# -STM32F1-3_0.net
KiCad netlist of a schematic drawn in EasyEDA Pro
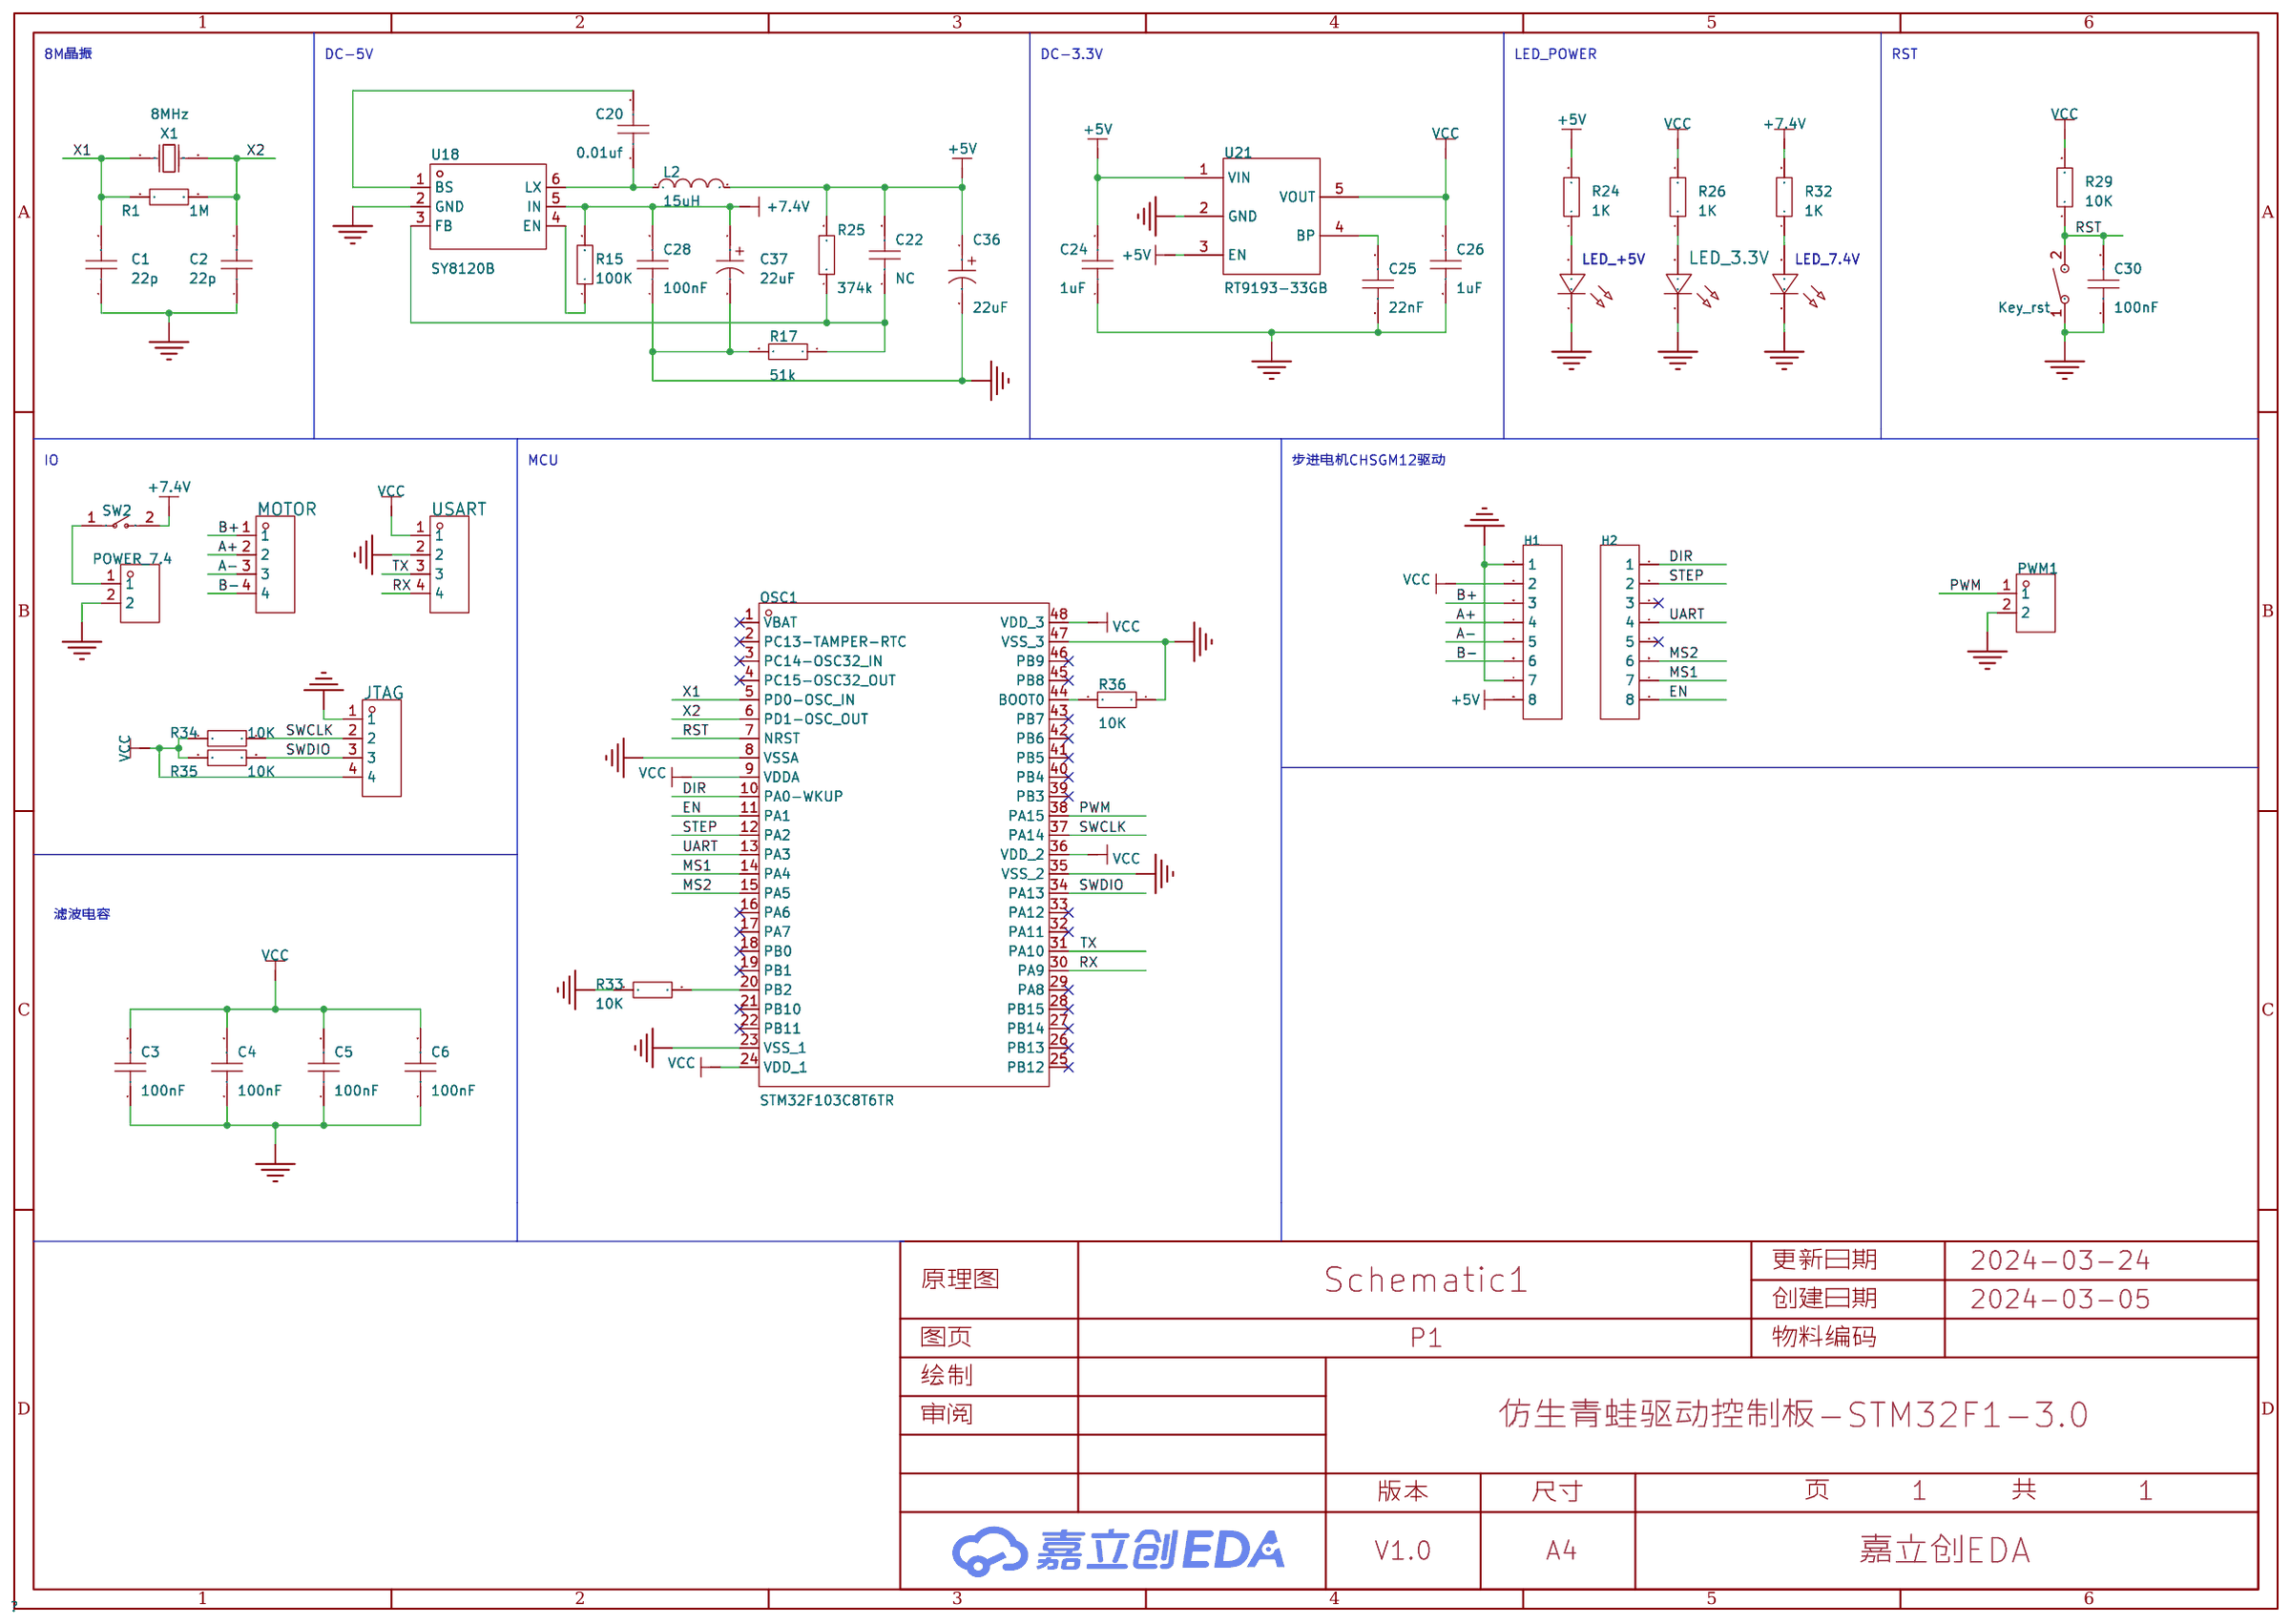
[diagram p0: schematic sheet]

(export (version "E")
  (design (tool "Eeschema 10.0.6"))
  (components
    (comp (ref "C1")
      (value "22p")
      (footprint "easyedapro:c0603")
      (libsource (lib "easyedapro") (part "CapAcitance"))
    )
    (comp (ref "C2")
      (value "22p")
      (footprint "easyedapro:c0603")
      (libsource (lib "easyedapro") (part "CapAcitance"))
    )
    (comp (ref "C3")
      (value "100nF")
      (footprint "easyedapro:c0603")
      (libsource (lib "easyedapro") (part "CapAcitance"))
    )
    (comp (ref "C4")
      (value "100nF")
      (footprint "easyedapro:c0603")
      (libsource (lib "easyedapro") (part "CapAcitance"))
    )
    (comp (ref "C5")
      (value "100nF")
      (footprint "easyedapro:c0603")
      (libsource (lib "easyedapro") (part "CapAcitance"))
    )
    (comp (ref "C6")
      (value "100nF")
      (footprint "easyedapro:c0603")
      (libsource (lib "easyedapro") (part "CapAcitance"))
    )
    (comp (ref "C20")
      (value "0.01uf")
      (footprint "easyedapro:C0805")
      (libsource (lib "easyedapro") (part "CapAcitance"))
    )
    (comp (ref "C22")
      (value "NC")
      (footprint "easyedapro:C0805")
      (libsource (lib "easyedapro") (part "CapAcitance"))
    )
    (comp (ref "C24")
      (value "1uF")
      (footprint "easyedapro:c0603")
      (libsource (lib "easyedapro") (part "CapAcitance"))
    )
    (comp (ref "C25")
      (value "22nF")
      (footprint "easyedapro:c0603")
      (libsource (lib "easyedapro") (part "CapAcitance"))
    )
    (comp (ref "C26")
      (value "1uF")
      (footprint "easyedapro:c0603")
      (libsource (lib "easyedapro") (part "CapAcitance"))
    )
    (comp (ref "C28")
      (value "100nF")
      (footprint "easyedapro:c0603")
      (libsource (lib "easyedapro") (part "CapAcitance"))
    )
    (comp (ref "C30")
      (value "100nF")
      (footprint "easyedapro:c0603")
      (libsource (lib "easyedapro") (part "CapAcitance"))
    )
    (comp (ref "C36")
      (value "22uF")
      (footprint "easyedapro:CAP-SMD_BD5.0-L5.3-W5.3-LS6.0-FD")
      (description "容值:22uF;精度:±20%;额定电压:25V;纹波电流:26mA@120Hz;等效串联电阻:-;")
      (fields
        (field (name "Manufacturer Part") "RVT22UF25V67RV0047")
        (field (name "Manufacturer") "KNSCHA(科尼盛)")
      )
      (libsource (lib "easyedapro") (part "RVT22UF25V67RV0047"))
    )
    (comp (ref "C37")
      (value "22uF")
      (footprint "easyedapro:CAP-SMD_BD5.0-L5.3-W5.3-LS6.0-FD")
      (description "容值:22uF;精度:±20%;额定电压:25V;纹波电流:26mA@120Hz;等效串联电阻:-;")
      (fields
        (field (name "Manufacturer Part") "RVT22UF25V67RV0047")
        (field (name "Manufacturer") "KNSCHA(科尼盛)")
      )
      (libsource (lib "easyedapro") (part "RVT22UF25V67RV0047"))
    )
    (comp (ref "H1")
      (value "~")
      (footprint "easyedapro:HDR-TH_8P-P2.54-V-F-1")
      (libsource (lib "easyedapro") (part "Header-Female-2.54_1x8"))
    )
    (comp (ref "H2")
      (value "~")
      (footprint "easyedapro:HDR-TH_8P-P2.54-V-F-1")
      (libsource (lib "easyedapro") (part "Header-Female-2.54_1x8"))
    )
    (comp (ref "JTAG")
      (value "~")
      (footprint "easyedapro:HDR-TH_4P-P2.54-V-F")
      (libsource (lib "easyedapro") (part "2.54-1*4P母"))
    )
    (comp (ref "Key_rst")
      (value "TS-1092S-B3D2-G")
      (footprint "easyedapro:SW-SMD_L6.1-W3.6-LS7.9")
      (description "电路结构:单刀单掷;按钮形状:矩形按钮;作用力:250gf;安装方式:立贴;开关长度:6.1mm;开关宽度:3.6mm;开关高度:2.5mm;带支架:不带;机械寿命:-;")
      (fields (field (name "Manufacturer") "Yuandi(元迪)"))
      (libsource (lib "easyedapro") (part "TS-1092S-B3D2-G"))
    )
    (comp (ref "L2")
      (value "15uH")
      (footprint "easyedapro:IND-SMD_L7.0-W6.6_FXL0630")
      (description "电感值:15uH;精度:±20%;额定电流:3A;饱和电流(Isat):4.5A;类型:一体成型电感;")
      (fields (field (name "Manufacturer Part") "FXL0630-150-M") (field (name "Manufacturer") "cjiang(长江微电)"))
      (libsource (lib "easyedapro") (part "FXL0630-150-M"))
    )
    (comp (ref "LED_+5V")
      (value "~")
      (footprint "easyedapro:LED_0603")
      (libsource (lib "easyedapro") (part "LED_G"))
    )
    (comp (ref "LED_3.3V")
      (value "~")
      (footprint "easyedapro:LED_0402")
      (libsource (lib "easyedapro") (part "LED_R"))
    )
    (comp (ref "LED_7.4V")
      (value "~")
      (footprint "easyedapro:LED_0402")
      (libsource (lib "easyedapro") (part "LED_B"))
    )
    (comp (ref "MOTOR")
      (value "~")
      (footprint "easyedapro:HDR-TH_4P-P2.54-V-F")
      (libsource (lib "easyedapro") (part "2.54-1*4P母"))
    )
    (comp (ref "OSC1")
      (value "STM32F103C8T6TR")
      (footprint "easyedapro:LQFP-48_L7.0-W7.0-P0.50-LS9.0-BL")
      (description "CPU内核:CM3;程序存储容量:64KB;RAM总容量:20KB;GPIO端口数量:37;工作电压范围:2V~3.6V;CPU最大主频:72MHz;程序存储器类型:-;")
      (fields (field (name "Manufacturer") "ST(意法半导体)"))
      (libsource (lib "easyedapro") (part "STM32F103C8T6TR"))
    )
    (comp (ref "POWER_7.4")
      (value "ZX-XH2.54-2PZZ")
      (footprint "easyedapro:CONN-TH_2P-P2.50_HX25003-2A")
      (fields (field (name "Manufacturer") "Megastar(兆星)"))
      (libsource (lib "easyedapro") (part "ZX-XH2.54-2PZZ"))
    )
    (comp (ref "PWM1")
      (value "ZX-XH2.54-2PZZ")
      (footprint "easyedapro:CONN-TH_2P-P2.50_HX25003-2A")
      (fields (field (name "Manufacturer") "Megastar(兆星)"))
      (libsource (lib "easyedapro") (part "ZX-XH2.54-2PZZ"))
    )
    (comp (ref "R1") (value "1M") (footprint "easyedapro:r0603") (libsource (lib "easyedapro") (part "电阻")))
    (comp (ref "R15")
      (value "100K")
      (footprint "easyedapro:R0805")
      (libsource (lib "easyedapro") (part "电阻"))
    )
    (comp (ref "R17") (value "51k") (footprint "easyedapro:R0805") (libsource (lib "easyedapro") (part "电阻")))
    (comp (ref "R24") (value "1K") (footprint "easyedapro:R0805") (libsource (lib "easyedapro") (part "电阻")))
    (comp (ref "R25")
      (value "374k")
      (footprint "easyedapro:R0805")
      (libsource (lib "easyedapro") (part "电阻"))
    )
    (comp (ref "R26") (value "1K") (footprint "easyedapro:r0603") (libsource (lib "easyedapro") (part "电阻")))
    (comp (ref "R29") (value "10K") (footprint "easyedapro:r0603") (libsource (lib "easyedapro") (part "电阻")))
    (comp (ref "R32") (value "1K") (footprint "easyedapro:r0603") (libsource (lib "easyedapro") (part "电阻")))
    (comp (ref "R33") (value "10K") (footprint "easyedapro:r0603") (libsource (lib "easyedapro") (part "电阻")))
    (comp (ref "R34") (value "10K") (footprint "easyedapro:r0603") (libsource (lib "easyedapro") (part "电阻")))
    (comp (ref "R35") (value "10K") (footprint "easyedapro:r0603") (libsource (lib "easyedapro") (part "电阻")))
    (comp (ref "R36") (value "10K") (footprint "easyedapro:r0603") (libsource (lib "easyedapro") (part "电阻")))
    (comp (ref "SW2")
      (value "KCD11-2P-R")
      (footprint "easyedapro:SW-TH_2P-L15.0-W10.5-P5.00_KCD11-2P-R")
      (description "带灯:无;引脚样式:焊片;额定电流:3A;额定电压(AC):250V;额定电压(DC):-;电路结构:单刀单掷;机械寿命:1万次;")
      (fields (field (name "Manufacturer") "SHOU HAN(首韩)"))
      (libsource (lib "easyedapro") (part "KCD11-2P-R"))
    )
    (comp (ref "U18")
      (value "SY8120B")
      (footprint "easyedapro:SOT-23-6_L2.9-W1.6-P0.95-LS2.8-BL")
      (fields (field (name "Manufacturer") "Slkor(萨科微)"))
      (libsource (lib "easyedapro") (part "SY8120B"))
    )
    (comp (ref "U21")
      (value "RT9193-33GB")
      (footprint "easyedapro:SOT-23-5_L3.0-W1.7-P0.95-LS2.8-BL")
      (description "输出类型:固定;最大输入电压:5.5V;输出电压:3.3V;最大输出电流:300mA;电源纹波抑制比(PSRR):70dB;输出极性:正极;")
      (fields (field (name "Manufacturer") "RICHTEK(立锜)"))
      (libsource (lib "easyedapro") (part "RT9193-33GB"))
    )
    (comp (ref "USART")
      (value "~")
      (footprint "easyedapro:HDR-TH_4P-P2.54-V-F")
      (libsource (lib "easyedapro") (part "2.54-1*4P母"))
    )
    (comp (ref "X1")
      (value "8MHz")
      (footprint "easyedapro:CRYSTAL-SMD_L5.0-W3.2")
      (description "晶振类型:贴片晶振;频率:8MHz;常温频差:±10ppm;外接负载电容:20pF;频率稳定度(全温):±50ppm;")
      (fields (field (name "Manufacturer Part") "X50328MSB2GI") (field (name "Manufacturer") "YXC(扬兴晶振)"))
      (libsource (lib "easyedapro") (part "X50328MSB2GI"))
    )
  )
  (nets
    (net (code "1") (name "+5V") (class "Default")
      (node (ref "C22") (pin "2") (pinfunction "2_2") (pintype "input"))
      (node (ref "C24") (pin "2") (pinfunction "2_2") (pintype "input"))
      (node (ref "C36") (pin "1") (pinfunction "1_1") (pintype "input"))
      (node (ref "H1") (pin "8") (pinfunction "8_8") (pintype "input"))
      (node (ref "L2") (pin "2") (pinfunction "2_2") (pintype "unspecified"))
      (node (ref "R24") (pin "2") (pinfunction "2_2") (pintype "input"))
      (node (ref "R25") (pin "2") (pinfunction "2_2") (pintype "input"))
      (node (ref "U21") (pin "1") (pinfunction "VIN_1") (pintype "unspecified"))
      (node (ref "U21") (pin "3") (pinfunction "EN_3") (pintype "unspecified"))
    )
    (net (code "2") (name "+7.4V") (class "Default")
      (node (ref "C28") (pin "2") (pinfunction "2_2") (pintype "input"))
      (node (ref "C37") (pin "1") (pinfunction "1_1") (pintype "input"))
      (node (ref "R15") (pin "2") (pinfunction "2_2") (pintype "input"))
      (node (ref "R32") (pin "2") (pinfunction "2_2") (pintype "input"))
      (node (ref "SW2") (pin "2") (pinfunction "2_2") (pintype "unspecified"))
      (node (ref "U18") (pin "5") (pinfunction "IN_5") (pintype "unspecified"))
    )
    (net (code "3") (name "/A+") (class "Default")
      (node (ref "H1") (pin "4") (pinfunction "4_4") (pintype "input"))
      (node (ref "MOTOR") (pin "2") (pinfunction "2_2") (pintype "input"))
    )
    (net (code "4") (name "/A-") (class "Default")
      (node (ref "H1") (pin "5") (pinfunction "5_5") (pintype "input"))
      (node (ref "MOTOR") (pin "3") (pinfunction "3_3") (pintype "input"))
    )
    (net (code "5") (name "/B+") (class "Default")
      (node (ref "H1") (pin "3") (pinfunction "3_3") (pintype "input"))
      (node (ref "MOTOR") (pin "1") (pinfunction "1_1") (pintype "input"))
    )
    (net (code "6") (name "/B-") (class "Default")
      (node (ref "H1") (pin "6") (pinfunction "6_6") (pintype "input"))
      (node (ref "MOTOR") (pin "4") (pinfunction "4_4") (pintype "input"))
    )
    (net (code "7") (name "/DIR") (class "Default")
      (node (ref "H2") (pin "1") (pinfunction "1_1") (pintype "input"))
      (node (ref "OSC1") (pin "10") (pinfunction "PA0-WKUP_10") (pintype "unspecified"))
    )
    (net (code "8") (name "/EN") (class "Default")
      (node (ref "H2") (pin "8") (pinfunction "8_8") (pintype "input"))
      (node (ref "OSC1") (pin "11") (pinfunction "PA1_11") (pintype "unspecified"))
    )
    (net (code "9") (name "/MS1") (class "Default")
      (node (ref "H2") (pin "7") (pinfunction "7_7") (pintype "input"))
      (node (ref "OSC1") (pin "14") (pinfunction "PA4_14") (pintype "unspecified"))
    )
    (net (code "10") (name "/MS2") (class "Default")
      (node (ref "H2") (pin "6") (pinfunction "6_6") (pintype "input"))
      (node (ref "OSC1") (pin "15") (pinfunction "PA5_15") (pintype "unspecified"))
    )
    (net (code "11") (name "/PWM") (class "Default")
      (node (ref "OSC1") (pin "38") (pinfunction "PA15_38") (pintype "unspecified"))
      (node (ref "PWM1") (pin "1") (pinfunction "1_1") (pintype "unspecified"))
    )
    (net (code "12") (name "/RST") (class "Default")
      (node (ref "C30") (pin "2") (pinfunction "2_2") (pintype "input"))
      (node (ref "Key_rst") (pin "2") (pinfunction "2_2") (pintype "unspecified"))
      (node (ref "OSC1") (pin "7") (pinfunction "NRST_7") (pintype "unspecified"))
      (node (ref "R29") (pin "1") (pinfunction "1_1") (pintype "input"))
    )
    (net (code "13") (name "/RX") (class "Default")
      (node (ref "OSC1") (pin "30") (pinfunction "PA9_30") (pintype "unspecified"))
      (node (ref "USART") (pin "4") (pinfunction "4_4") (pintype "input"))
    )
    (net (code "14") (name "/STEP") (class "Default")
      (node (ref "H2") (pin "2") (pinfunction "2_2") (pintype "input"))
      (node (ref "OSC1") (pin "12") (pinfunction "PA2_12") (pintype "unspecified"))
    )
    (net (code "15") (name "/SWCLK") (class "Default")
      (node (ref "JTAG") (pin "2") (pinfunction "2_2") (pintype "input"))
      (node (ref "OSC1") (pin "37") (pinfunction "PA14_37") (pintype "unspecified"))
      (node (ref "R34") (pin "2") (pinfunction "2_2") (pintype "input"))
    )
    (net (code "16") (name "/SWDIO") (class "Default")
      (node (ref "JTAG") (pin "3") (pinfunction "3_3") (pintype "input"))
      (node (ref "OSC1") (pin "34") (pinfunction "PA13_34") (pintype "unspecified"))
      (node (ref "R35") (pin "2") (pinfunction "2_2") (pintype "input"))
    )
    (net (code "17") (name "/TX") (class "Default")
      (node (ref "OSC1") (pin "31") (pinfunction "PA10_31") (pintype "unspecified"))
      (node (ref "USART") (pin "3") (pinfunction "3_3") (pintype "input"))
    )
    (net (code "18") (name "/UART") (class "Default")
      (node (ref "H2") (pin "4") (pinfunction "4_4") (pintype "input"))
      (node (ref "OSC1") (pin "13") (pinfunction "PA3_13") (pintype "unspecified"))
    )
    (net (code "19") (name "/X1") (class "Default")
      (node (ref "C1") (pin "2") (pinfunction "2_2") (pintype "input"))
      (node (ref "OSC1") (pin "5") (pinfunction "PD0-OSC_IN_5") (pintype "unspecified"))
      (node (ref "R1") (pin "1") (pinfunction "1_1") (pintype "input"))
      (node (ref "X1") (pin "1") (pinfunction "OSC1_1") (pintype "input"))
    )
    (net (code "20") (name "/X2") (class "Default")
      (node (ref "C2") (pin "2") (pinfunction "2_2") (pintype "input"))
      (node (ref "OSC1") (pin "6") (pinfunction "PD1-OSC_OUT_6") (pintype "unspecified"))
      (node (ref "R1") (pin "2") (pinfunction "2_2") (pintype "input"))
      (node (ref "X1") (pin "2") (pinfunction "OSC2_2") (pintype "input"))
    )
    (net (code "21") (name "GND") (class "Default")
      (node (ref "C1") (pin "1") (pinfunction "1_1") (pintype "input"))
      (node (ref "C2") (pin "1") (pinfunction "1_1") (pintype "input"))
      (node (ref "C24") (pin "1") (pinfunction "1_1") (pintype "input"))
      (node (ref "C25") (pin "2") (pinfunction "2_2") (pintype "input"))
      (node (ref "C26") (pin "2") (pinfunction "2_2") (pintype "input"))
      (node (ref "C28") (pin "1") (pinfunction "1_1") (pintype "input"))
      (node (ref "C3") (pin "1") (pinfunction "1_1") (pintype "input"))
      (node (ref "C30") (pin "1") (pinfunction "1_1") (pintype "input"))
      (node (ref "C36") (pin "2") (pinfunction "2_2") (pintype "input"))
      (node (ref "C37") (pin "2") (pinfunction "2_2") (pintype "input"))
      (node (ref "C4") (pin "1") (pinfunction "1_1") (pintype "input"))
      (node (ref "C5") (pin "1") (pinfunction "1_1") (pintype "input"))
      (node (ref "C6") (pin "1") (pinfunction "1_1") (pintype "input"))
      (node (ref "H1") (pin "1") (pinfunction "1_1") (pintype "input"))
      (node (ref "H1") (pin "7") (pinfunction "7_7") (pintype "input"))
      (node (ref "JTAG") (pin "1") (pinfunction "1_1") (pintype "input"))
      (node (ref "Key_rst") (pin "1") (pinfunction "1_1") (pintype "unspecified"))
      (node (ref "LED_+5V") (pin "1") (pinfunction "C_1") (pintype "input"))
      (node (ref "LED_3.3V") (pin "1") (pinfunction "C_1") (pintype "input"))
      (node (ref "LED_7.4V") (pin "1") (pinfunction "C_1") (pintype "input"))
      (node (ref "OSC1") (pin "23") (pinfunction "VSS_1_23") (pintype "unspecified"))
      (node (ref "OSC1") (pin "35") (pinfunction "VSS_2_35") (pintype "unspecified"))
      (node (ref "OSC1") (pin "47") (pinfunction "VSS_3_47") (pintype "unspecified"))
      (node (ref "OSC1") (pin "8") (pinfunction "VSSA_8") (pintype "unspecified"))
      (node (ref "POWER_7.4") (pin "2") (pinfunction "2_2") (pintype "unspecified"))
      (node (ref "PWM1") (pin "2") (pinfunction "2_2") (pintype "unspecified"))
      (node (ref "R17") (pin "2") (pinfunction "2_2") (pintype "input"))
      (node (ref "R33") (pin "1") (pinfunction "1_1") (pintype "input"))
      (node (ref "R36") (pin "1") (pinfunction "1_1") (pintype "input"))
      (node (ref "U18") (pin "2") (pinfunction "GND_2") (pintype "unspecified"))
      (node (ref "U21") (pin "2") (pinfunction "GND_2") (pintype "unspecified"))
      (node (ref "USART") (pin "2") (pinfunction "2_2") (pintype "input"))
    )
    (net (code "22") (name "Net-(LED_+5V-A)") (class "Default")
      (node (ref "LED_+5V") (pin "2") (pinfunction "A_2") (pintype "input"))
      (node (ref "R24") (pin "1") (pinfunction "1_1") (pintype "input"))
    )
    (net (code "23") (name "Net-(LED_3.3V-A)") (class "Default")
      (node (ref "LED_3.3V") (pin "2") (pinfunction "A_2") (pintype "input"))
      (node (ref "R26") (pin "1") (pinfunction "1_1") (pintype "input"))
    )
    (net (code "24") (name "Net-(LED_7.4V-A)") (class "Default")
      (node (ref "LED_7.4V") (pin "2") (pinfunction "A_2") (pintype "input"))
      (node (ref "R32") (pin "1") (pinfunction "1_1") (pintype "input"))
    )
    (net (code "25") (name "Net-(OSC1-BOOT0)") (class "Default")
      (node (ref "OSC1") (pin "44") (pinfunction "BOOT0_44") (pintype "unspecified"))
      (node (ref "R36") (pin "2") (pinfunction "2_2") (pintype "input"))
    )
    (net (code "26") (name "Net-(OSC1-PB2)") (class "Default")
      (node (ref "OSC1") (pin "20") (pinfunction "PB2_20") (pintype "unspecified"))
      (node (ref "R33") (pin "2") (pinfunction "2_2") (pintype "input"))
    )
    (net (code "27") (name "Net-(POWER_7.4-Pad1)") (class "Default")
      (node (ref "POWER_7.4") (pin "1") (pinfunction "1_1") (pintype "unspecified"))
      (node (ref "SW2") (pin "1") (pinfunction "1_1") (pintype "unspecified"))
    )
    (net (code "28") (name "Net-(U18-BS)") (class "Default")
      (node (ref "C20") (pin "2") (pinfunction "2_2") (pintype "input"))
      (node (ref "U18") (pin "1") (pinfunction "BS_1") (pintype "unspecified"))
    )
    (net (code "29") (name "Net-(U18-EN)") (class "Default")
      (node (ref "R15") (pin "1") (pinfunction "1_1") (pintype "input"))
      (node (ref "U18") (pin "4") (pinfunction "EN_4") (pintype "unspecified"))
    )
    (net (code "30") (name "Net-(U18-FB)") (class "Default")
      (node (ref "C22") (pin "1") (pinfunction "1_1") (pintype "input"))
      (node (ref "R17") (pin "1") (pinfunction "1_1") (pintype "input"))
      (node (ref "R25") (pin "1") (pinfunction "1_1") (pintype "input"))
      (node (ref "U18") (pin "3") (pinfunction "FB_3") (pintype "unspecified"))
    )
    (net (code "31") (name "Net-(U18-LX)") (class "Default")
      (node (ref "C20") (pin "1") (pinfunction "1_1") (pintype "input"))
      (node (ref "L2") (pin "1") (pinfunction "1_1") (pintype "unspecified"))
      (node (ref "U18") (pin "6") (pinfunction "LX_6") (pintype "unspecified"))
    )
    (net (code "32") (name "Net-(U21-BP)") (class "Default")
      (node (ref "C25") (pin "1") (pinfunction "1_1") (pintype "input"))
      (node (ref "U21") (pin "4") (pinfunction "BP_4") (pintype "unspecified"))
    )
    (net (code "33") (name "VCC") (class "Default")
      (node (ref "C26") (pin "1") (pinfunction "1_1") (pintype "input"))
      (node (ref "C3") (pin "2") (pinfunction "2_2") (pintype "input"))
      (node (ref "C4") (pin "2") (pinfunction "2_2") (pintype "input"))
      (node (ref "C5") (pin "2") (pinfunction "2_2") (pintype "input"))
      (node (ref "C6") (pin "2") (pinfunction "2_2") (pintype "input"))
      (node (ref "H1") (pin "2") (pinfunction "2_2") (pintype "input"))
      (node (ref "JTAG") (pin "4") (pinfunction "4_4") (pintype "input"))
      (node (ref "OSC1") (pin "24") (pinfunction "VDD_1_24") (pintype "unspecified"))
      (node (ref "OSC1") (pin "36") (pinfunction "VDD_2_36") (pintype "unspecified"))
      (node (ref "OSC1") (pin "48") (pinfunction "VDD_3_48") (pintype "unspecified"))
      (node (ref "OSC1") (pin "9") (pinfunction "VDDA_9") (pintype "unspecified"))
      (node (ref "R26") (pin "2") (pinfunction "2_2") (pintype "input"))
      (node (ref "R29") (pin "2") (pinfunction "2_2") (pintype "input"))
      (node (ref "R34") (pin "1") (pinfunction "1_1") (pintype "input"))
      (node (ref "R35") (pin "1") (pinfunction "1_1") (pintype "input"))
      (node (ref "U21") (pin "5") (pinfunction "VOUT_5") (pintype "unspecified"))
      (node (ref "USART") (pin "1") (pinfunction "1_1") (pintype "input"))
    )
    (net (code "34") (name "unconnected-(H2-Pad3)") (class "Default")
      (node (ref "H2") (pin "3") (pinfunction "3_3") (pintype "input+no_connect"))
    )
    (net (code "35") (name "unconnected-(H2-Pad5)") (class "Default")
      (node (ref "H2") (pin "5") (pinfunction "5_5") (pintype "input+no_connect"))
    )
    (net (code "36") (name "unconnected-(OSC1-PA6-Pad16)") (class "Default")
      (node (ref "OSC1") (pin "16") (pinfunction "PA6_16") (pintype "unspecified+no_connect"))
    )
    (net (code "37") (name "unconnected-(OSC1-PA7-Pad17)") (class "Default")
      (node (ref "OSC1") (pin "17") (pinfunction "PA7_17") (pintype "unspecified+no_connect"))
    )
    (net (code "38") (name "unconnected-(OSC1-PA8-Pad29)") (class "Default")
      (node (ref "OSC1") (pin "29") (pinfunction "PA8_29") (pintype "unspecified+no_connect"))
    )
    (net (code "39") (name "unconnected-(OSC1-PA11-Pad32)") (class "Default")
      (node (ref "OSC1") (pin "32") (pinfunction "PA11_32") (pintype "unspecified+no_connect"))
    )
    (net (code "40") (name "unconnected-(OSC1-PA12-Pad33)") (class "Default")
      (node (ref "OSC1") (pin "33") (pinfunction "PA12_33") (pintype "unspecified+no_connect"))
    )
    (net (code "41") (name "unconnected-(OSC1-PB0-Pad18)") (class "Default")
      (node (ref "OSC1") (pin "18") (pinfunction "PB0_18") (pintype "unspecified+no_connect"))
    )
    (net (code "42") (name "unconnected-(OSC1-PB1-Pad19)") (class "Default")
      (node (ref "OSC1") (pin "19") (pinfunction "PB1_19") (pintype "unspecified+no_connect"))
    )
    (net (code "43") (name "unconnected-(OSC1-PB3-Pad39)") (class "Default")
      (node (ref "OSC1") (pin "39") (pinfunction "PB3_39") (pintype "unspecified+no_connect"))
    )
    (net (code "44") (name "unconnected-(OSC1-PB4-Pad40)") (class "Default")
      (node (ref "OSC1") (pin "40") (pinfunction "PB4_40") (pintype "unspecified+no_connect"))
    )
    (net (code "45") (name "unconnected-(OSC1-PB5-Pad41)") (class "Default")
      (node (ref "OSC1") (pin "41") (pinfunction "PB5_41") (pintype "unspecified+no_connect"))
    )
    (net (code "46") (name "unconnected-(OSC1-PB6-Pad42)") (class "Default")
      (node (ref "OSC1") (pin "42") (pinfunction "PB6_42") (pintype "unspecified+no_connect"))
    )
    (net (code "47") (name "unconnected-(OSC1-PB7-Pad43)") (class "Default")
      (node (ref "OSC1") (pin "43") (pinfunction "PB7_43") (pintype "unspecified+no_connect"))
    )
    (net (code "48") (name "unconnected-(OSC1-PB8-Pad45)") (class "Default")
      (node (ref "OSC1") (pin "45") (pinfunction "PB8_45") (pintype "unspecified+no_connect"))
    )
    (net (code "49") (name "unconnected-(OSC1-PB9-Pad46)") (class "Default")
      (node (ref "OSC1") (pin "46") (pinfunction "PB9_46") (pintype "unspecified+no_connect"))
    )
    (net (code "50") (name "unconnected-(OSC1-PB10-Pad21)") (class "Default")
      (node (ref "OSC1") (pin "21") (pinfunction "PB10_21") (pintype "unspecified+no_connect"))
    )
    (net (code "51") (name "unconnected-(OSC1-PB11-Pad22)") (class "Default")
      (node (ref "OSC1") (pin "22") (pinfunction "PB11_22") (pintype "unspecified+no_connect"))
    )
    (net (code "52") (name "unconnected-(OSC1-PB12-Pad25)") (class "Default")
      (node (ref "OSC1") (pin "25") (pinfunction "PB12_25") (pintype "unspecified+no_connect"))
    )
    (net (code "53") (name "unconnected-(OSC1-PB13-Pad26)") (class "Default")
      (node (ref "OSC1") (pin "26") (pinfunction "PB13_26") (pintype "unspecified+no_connect"))
    )
    (net (code "54") (name "unconnected-(OSC1-PB14-Pad27)") (class "Default")
      (node (ref "OSC1") (pin "27") (pinfunction "PB14_27") (pintype "unspecified+no_connect"))
    )
    (net (code "55") (name "unconnected-(OSC1-PB15-Pad28)") (class "Default")
      (node (ref "OSC1") (pin "28") (pinfunction "PB15_28") (pintype "unspecified+no_connect"))
    )
    (net (code "56") (name "unconnected-(OSC1-PC13-TAMPER-RTC-Pad2)") (class "Default")
      (node (ref "OSC1") (pin "2") (pinfunction "PC13-TAMPER-RTC_2") (pintype "unspecified+no_connect"))
    )
    (net (code "57") (name "unconnected-(OSC1-PC14-OSC32_IN-Pad3)") (class "Default")
      (node (ref "OSC1") (pin "3") (pinfunction "PC14-OSC32_IN_3") (pintype "unspecified+no_connect"))
    )
    (net (code "58") (name "unconnected-(OSC1-PC15-OSC32_OUT-Pad4)") (class "Default")
      (node (ref "OSC1") (pin "4") (pinfunction "PC15-OSC32_OUT_4") (pintype "unspecified+no_connect"))
    )
    (net (code "59") (name "unconnected-(OSC1-VBAT-Pad1)") (class "Default")
      (node (ref "OSC1") (pin "1") (pinfunction "VBAT_1") (pintype "unspecified+no_connect"))
    )
  )
)
